# sch_buttons.net
KiCad netlist of a schematic drawn in EasyEDA
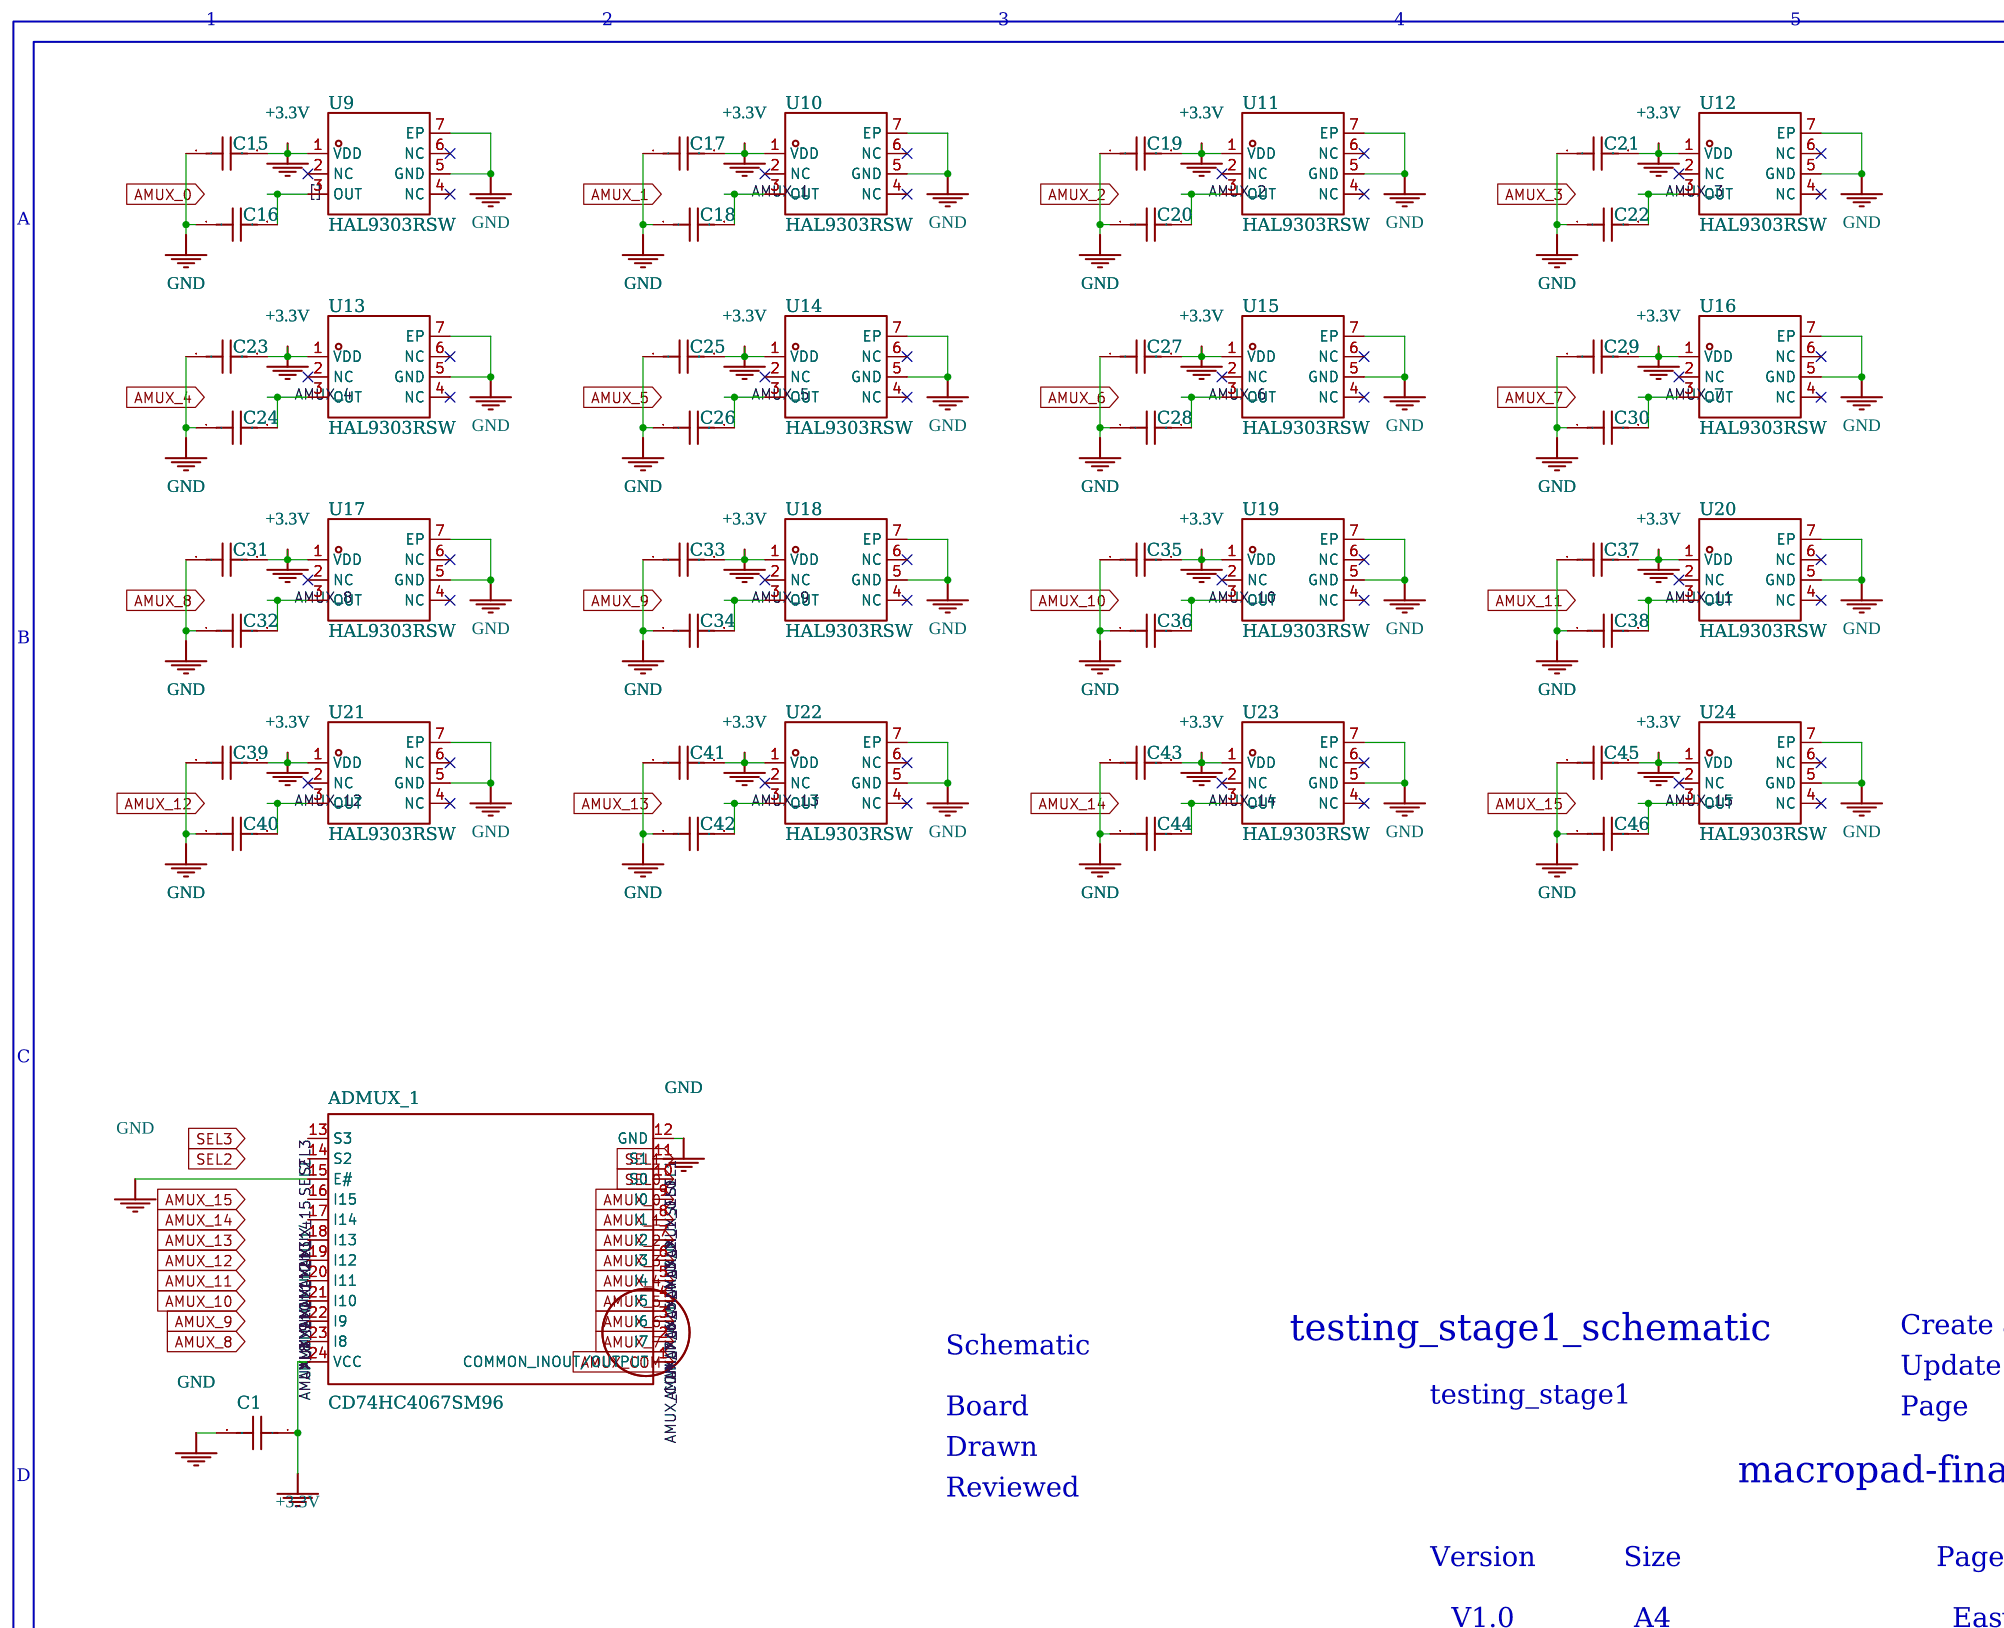
[diagram p0: schematic sheet]

(export (version "E")
  (design (tool "Eeschema 10.0.6"))
  (components
    (comp (ref "ADMUX_1")
      (value "CD74HC4067SM96")
      (fields (field (name "Manufacturer") "TI(德州仪器)"))
      (libsource (lib "") (part "Unknown_255_-240"))
    )
    (comp (ref "C1")
      (value "100nF")
      (fields
        (field (name "Manufacturer Part") "TCC0201X7R104K160ZT")
        (field (name "Manufacturer") "CCTC(三环)")
      )
      (libsource (lib "") (part "Unknown_140_-150"))
    )
    (comp (ref "C15")
      (value "100nF")
      (fields
        (field (name "Manufacturer Part") "TCC0201X7R104K160ZT")
        (field (name "Manufacturer") "CCTC(三环)")
      )
      (libsource (lib "") (part "Unknown_125_-780"))
    )
    (comp (ref "C16")
      (value "100nF")
      (fields
        (field (name "Manufacturer Part") "TCC0201X7R104K160ZT")
        (field (name "Manufacturer") "CCTC(三环)")
      )
      (libsource (lib "") (part "Unknown_130_-745"))
    )
    (comp (ref "C17")
      (value "100nF")
      (fields
        (field (name "Manufacturer Part") "TCC0201X7R104K160ZT")
        (field (name "Manufacturer") "CCTC(三环)")
      )
      (libsource (lib "") (part "Unknown_350_-780"))
    )
    (comp (ref "C18")
      (value "100nF")
      (fields
        (field (name "Manufacturer Part") "TCC0201X7R104K160ZT")
        (field (name "Manufacturer") "CCTC(三环)")
      )
      (libsource (lib "") (part "Unknown_355_-745"))
    )
    (comp (ref "C19")
      (value "100nF")
      (fields
        (field (name "Manufacturer Part") "TCC0201X7R104K160ZT")
        (field (name "Manufacturer") "CCTC(三环)")
      )
      (libsource (lib "") (part "Unknown_575_-780"))
    )
    (comp (ref "C20")
      (value "100nF")
      (fields
        (field (name "Manufacturer Part") "TCC0201X7R104K160ZT")
        (field (name "Manufacturer") "CCTC(三环)")
      )
      (libsource (lib "") (part "Unknown_580_-745"))
    )
    (comp (ref "C21")
      (value "100nF")
      (fields
        (field (name "Manufacturer Part") "TCC0201X7R104K160ZT")
        (field (name "Manufacturer") "CCTC(三环)")
      )
      (libsource (lib "") (part "Unknown_800_-780"))
    )
    (comp (ref "C22")
      (value "100nF")
      (fields
        (field (name "Manufacturer Part") "TCC0201X7R104K160ZT")
        (field (name "Manufacturer") "CCTC(三环)")
      )
      (libsource (lib "") (part "Unknown_805_-745"))
    )
    (comp (ref "C23")
      (value "100nF")
      (fields
        (field (name "Manufacturer Part") "TCC0201X7R104K160ZT")
        (field (name "Manufacturer") "CCTC(三环)")
      )
      (libsource (lib "") (part "Unknown_125_-680"))
    )
    (comp (ref "C24")
      (value "100nF")
      (fields
        (field (name "Manufacturer Part") "TCC0201X7R104K160ZT")
        (field (name "Manufacturer") "CCTC(三环)")
      )
      (libsource (lib "") (part "Unknown_130_-645"))
    )
    (comp (ref "C25")
      (value "100nF")
      (fields
        (field (name "Manufacturer Part") "TCC0201X7R104K160ZT")
        (field (name "Manufacturer") "CCTC(三环)")
      )
      (libsource (lib "") (part "Unknown_350_-680"))
    )
    (comp (ref "C26")
      (value "100nF")
      (fields
        (field (name "Manufacturer Part") "TCC0201X7R104K160ZT")
        (field (name "Manufacturer") "CCTC(三环)")
      )
      (libsource (lib "") (part "Unknown_355_-645"))
    )
    (comp (ref "C27")
      (value "100nF")
      (fields
        (field (name "Manufacturer Part") "TCC0201X7R104K160ZT")
        (field (name "Manufacturer") "CCTC(三环)")
      )
      (libsource (lib "") (part "Unknown_575_-680"))
    )
    (comp (ref "C28")
      (value "100nF")
      (fields
        (field (name "Manufacturer Part") "TCC0201X7R104K160ZT")
        (field (name "Manufacturer") "CCTC(三环)")
      )
      (libsource (lib "") (part "Unknown_580_-645"))
    )
    (comp (ref "C29")
      (value "100nF")
      (fields
        (field (name "Manufacturer Part") "TCC0201X7R104K160ZT")
        (field (name "Manufacturer") "CCTC(三环)")
      )
      (libsource (lib "") (part "Unknown_800_-680"))
    )
    (comp (ref "C30")
      (value "100nF")
      (fields
        (field (name "Manufacturer Part") "TCC0201X7R104K160ZT")
        (field (name "Manufacturer") "CCTC(三环)")
      )
      (libsource (lib "") (part "Unknown_805_-645"))
    )
    (comp (ref "C31")
      (value "100nF")
      (fields
        (field (name "Manufacturer Part") "TCC0201X7R104K160ZT")
        (field (name "Manufacturer") "CCTC(三环)")
      )
      (libsource (lib "") (part "Unknown_125_-580"))
    )
    (comp (ref "C32")
      (value "100nF")
      (fields
        (field (name "Manufacturer Part") "TCC0201X7R104K160ZT")
        (field (name "Manufacturer") "CCTC(三环)")
      )
      (libsource (lib "") (part "Unknown_130_-545"))
    )
    (comp (ref "C33")
      (value "100nF")
      (fields
        (field (name "Manufacturer Part") "TCC0201X7R104K160ZT")
        (field (name "Manufacturer") "CCTC(三环)")
      )
      (libsource (lib "") (part "Unknown_350_-580"))
    )
    (comp (ref "C34")
      (value "100nF")
      (fields
        (field (name "Manufacturer Part") "TCC0201X7R104K160ZT")
        (field (name "Manufacturer") "CCTC(三环)")
      )
      (libsource (lib "") (part "Unknown_355_-545"))
    )
    (comp (ref "C35")
      (value "100nF")
      (fields
        (field (name "Manufacturer Part") "TCC0201X7R104K160ZT")
        (field (name "Manufacturer") "CCTC(三环)")
      )
      (libsource (lib "") (part "Unknown_575_-580"))
    )
    (comp (ref "C36")
      (value "100nF")
      (fields
        (field (name "Manufacturer Part") "TCC0201X7R104K160ZT")
        (field (name "Manufacturer") "CCTC(三环)")
      )
      (libsource (lib "") (part "Unknown_580_-545"))
    )
    (comp (ref "C37")
      (value "100nF")
      (fields
        (field (name "Manufacturer Part") "TCC0201X7R104K160ZT")
        (field (name "Manufacturer") "CCTC(三环)")
      )
      (libsource (lib "") (part "Unknown_800_-580"))
    )
    (comp (ref "C38")
      (value "100nF")
      (fields
        (field (name "Manufacturer Part") "TCC0201X7R104K160ZT")
        (field (name "Manufacturer") "CCTC(三环)")
      )
      (libsource (lib "") (part "Unknown_805_-545"))
    )
    (comp (ref "C39")
      (value "100nF")
      (fields
        (field (name "Manufacturer Part") "TCC0201X7R104K160ZT")
        (field (name "Manufacturer") "CCTC(三环)")
      )
      (libsource (lib "") (part "Unknown_125_-480"))
    )
    (comp (ref "C40")
      (value "100nF")
      (fields
        (field (name "Manufacturer Part") "TCC0201X7R104K160ZT")
        (field (name "Manufacturer") "CCTC(三环)")
      )
      (libsource (lib "") (part "Unknown_130_-445"))
    )
    (comp (ref "C41")
      (value "100nF")
      (fields
        (field (name "Manufacturer Part") "TCC0201X7R104K160ZT")
        (field (name "Manufacturer") "CCTC(三环)")
      )
      (libsource (lib "") (part "Unknown_350_-480"))
    )
    (comp (ref "C42")
      (value "100nF")
      (fields
        (field (name "Manufacturer Part") "TCC0201X7R104K160ZT")
        (field (name "Manufacturer") "CCTC(三环)")
      )
      (libsource (lib "") (part "Unknown_355_-445"))
    )
    (comp (ref "C43")
      (value "100nF")
      (fields
        (field (name "Manufacturer Part") "TCC0201X7R104K160ZT")
        (field (name "Manufacturer") "CCTC(三环)")
      )
      (libsource (lib "") (part "Unknown_575_-480"))
    )
    (comp (ref "C44")
      (value "100nF")
      (fields
        (field (name "Manufacturer Part") "TCC0201X7R104K160ZT")
        (field (name "Manufacturer") "CCTC(三环)")
      )
      (libsource (lib "") (part "Unknown_580_-445"))
    )
    (comp (ref "C45")
      (value "100nF")
      (fields
        (field (name "Manufacturer Part") "TCC0201X7R104K160ZT")
        (field (name "Manufacturer") "CCTC(三环)")
      )
      (libsource (lib "") (part "Unknown_800_-480"))
    )
    (comp (ref "C46")
      (value "100nF")
      (fields
        (field (name "Manufacturer Part") "TCC0201X7R104K160ZT")
        (field (name "Manufacturer") "CCTC(三环)")
      )
      (libsource (lib "") (part "Unknown_805_-445"))
    )
    (comp (ref "U9")
      (value "HAL9303RSW")
      (fields (field (name "Manufacturer") "Hallwee(霍尔微电子)"))
      (libsource (lib "") (part "Unknown_200_-775"))
    )
    (comp (ref "U10")
      (value "HAL9303RSW")
      (fields (field (name "Manufacturer") "Hallwee(霍尔微电子)"))
      (libsource (lib "") (part "Unknown_425_-775"))
    )
    (comp (ref "U11")
      (value "HAL9303RSW")
      (fields (field (name "Manufacturer") "Hallwee(霍尔微电子)"))
      (libsource (lib "") (part "Unknown_650_-775"))
    )
    (comp (ref "U12")
      (value "HAL9303RSW")
      (fields (field (name "Manufacturer") "Hallwee(霍尔微电子)"))
      (libsource (lib "") (part "Unknown_875_-775"))
    )
    (comp (ref "U13")
      (value "HAL9303RSW")
      (fields (field (name "Manufacturer") "Hallwee(霍尔微电子)"))
      (libsource (lib "") (part "Unknown_200_-675"))
    )
    (comp (ref "U14")
      (value "HAL9303RSW")
      (fields (field (name "Manufacturer") "Hallwee(霍尔微电子)"))
      (libsource (lib "") (part "Unknown_425_-675"))
    )
    (comp (ref "U15")
      (value "HAL9303RSW")
      (fields (field (name "Manufacturer") "Hallwee(霍尔微电子)"))
      (libsource (lib "") (part "Unknown_650_-675"))
    )
    (comp (ref "U16")
      (value "HAL9303RSW")
      (fields (field (name "Manufacturer") "Hallwee(霍尔微电子)"))
      (libsource (lib "") (part "Unknown_875_-675"))
    )
    (comp (ref "U17")
      (value "HAL9303RSW")
      (fields (field (name "Manufacturer") "Hallwee(霍尔微电子)"))
      (libsource (lib "") (part "Unknown_200_-575"))
    )
    (comp (ref "U18")
      (value "HAL9303RSW")
      (fields (field (name "Manufacturer") "Hallwee(霍尔微电子)"))
      (libsource (lib "") (part "Unknown_425_-575"))
    )
    (comp (ref "U19")
      (value "HAL9303RSW")
      (fields (field (name "Manufacturer") "Hallwee(霍尔微电子)"))
      (libsource (lib "") (part "Unknown_650_-575"))
    )
    (comp (ref "U20")
      (value "HAL9303RSW")
      (fields (field (name "Manufacturer") "Hallwee(霍尔微电子)"))
      (libsource (lib "") (part "Unknown_875_-575"))
    )
    (comp (ref "U21")
      (value "HAL9303RSW")
      (fields (field (name "Manufacturer") "Hallwee(霍尔微电子)"))
      (libsource (lib "") (part "Unknown_200_-475"))
    )
    (comp (ref "U22")
      (value "HAL9303RSW")
      (fields (field (name "Manufacturer") "Hallwee(霍尔微电子)"))
      (libsource (lib "") (part "Unknown_425_-475"))
    )
    (comp (ref "U23")
      (value "HAL9303RSW")
      (fields (field (name "Manufacturer") "Hallwee(霍尔微电子)"))
      (libsource (lib "") (part "Unknown_650_-475"))
    )
    (comp (ref "U24")
      (value "HAL9303RSW")
      (fields (field (name "Manufacturer") "Hallwee(霍尔微电子)"))
      (libsource (lib "") (part "Unknown_875_-475"))
    )
  )
  (nets
    (net (code "1") (name "+3.3V") (class "Default")
      (node (ref "ADMUX_1") (pin "24") (pinfunction "VCC_24") (pintype "unspecified"))
      (node (ref "C1") (pin "1") (pinfunction "1_1") (pintype "unspecified"))
      (node (ref "C15") (pin "2") (pinfunction "2_2") (pintype "unspecified"))
      (node (ref "C17") (pin "2") (pinfunction "2_2") (pintype "unspecified"))
      (node (ref "C19") (pin "2") (pinfunction "2_2") (pintype "unspecified"))
      (node (ref "C21") (pin "2") (pinfunction "2_2") (pintype "unspecified"))
      (node (ref "C23") (pin "2") (pinfunction "2_2") (pintype "unspecified"))
      (node (ref "C25") (pin "2") (pinfunction "2_2") (pintype "unspecified"))
      (node (ref "C27") (pin "2") (pinfunction "2_2") (pintype "unspecified"))
      (node (ref "C29") (pin "2") (pinfunction "2_2") (pintype "unspecified"))
      (node (ref "C31") (pin "2") (pinfunction "2_2") (pintype "unspecified"))
      (node (ref "C33") (pin "2") (pinfunction "2_2") (pintype "unspecified"))
      (node (ref "C35") (pin "2") (pinfunction "2_2") (pintype "unspecified"))
      (node (ref "C37") (pin "2") (pinfunction "2_2") (pintype "unspecified"))
      (node (ref "C39") (pin "2") (pinfunction "2_2") (pintype "unspecified"))
      (node (ref "C41") (pin "2") (pinfunction "2_2") (pintype "unspecified"))
      (node (ref "C43") (pin "2") (pinfunction "2_2") (pintype "unspecified"))
      (node (ref "C45") (pin "2") (pinfunction "2_2") (pintype "unspecified"))
      (node (ref "U10") (pin "1") (pinfunction "VDD_1") (pintype "unspecified"))
      (node (ref "U11") (pin "1") (pinfunction "VDD_1") (pintype "unspecified"))
      (node (ref "U12") (pin "1") (pinfunction "VDD_1") (pintype "unspecified"))
      (node (ref "U13") (pin "1") (pinfunction "VDD_1") (pintype "unspecified"))
      (node (ref "U14") (pin "1") (pinfunction "VDD_1") (pintype "unspecified"))
      (node (ref "U15") (pin "1") (pinfunction "VDD_1") (pintype "unspecified"))
      (node (ref "U16") (pin "1") (pinfunction "VDD_1") (pintype "unspecified"))
      (node (ref "U17") (pin "1") (pinfunction "VDD_1") (pintype "unspecified"))
      (node (ref "U18") (pin "1") (pinfunction "VDD_1") (pintype "unspecified"))
      (node (ref "U19") (pin "1") (pinfunction "VDD_1") (pintype "unspecified"))
      (node (ref "U20") (pin "1") (pinfunction "VDD_1") (pintype "unspecified"))
      (node (ref "U21") (pin "1") (pinfunction "VDD_1") (pintype "unspecified"))
      (node (ref "U22") (pin "1") (pinfunction "VDD_1") (pintype "unspecified"))
      (node (ref "U23") (pin "1") (pinfunction "VDD_1") (pintype "unspecified"))
      (node (ref "U24") (pin "1") (pinfunction "VDD_1") (pintype "unspecified"))
      (node (ref "U9") (pin "1") (pinfunction "VDD_1") (pintype "unspecified"))
    )
    (net (code "2") (name "/[]") (class "Default")
      (node (ref "C16") (pin "2") (pinfunction "2_2") (pintype "unspecified"))
      (node (ref "U9") (pin "3") (pinfunction "OUT_3") (pintype "unspecified"))
    )
    (net (code "3") (name "AMUX_0") (class "Default")
      (node (ref "ADMUX_1") (pin "9") (pinfunction "I0_9") (pintype "unspecified"))
    )
    (net (code "4") (name "AMUX_1") (class "Default")
      (node (ref "ADMUX_1") (pin "8") (pinfunction "I1_8") (pintype "unspecified"))
      (node (ref "C18") (pin "2") (pinfunction "2_2") (pintype "unspecified"))
      (node (ref "U10") (pin "3") (pinfunction "OUT_3") (pintype "unspecified"))
    )
    (net (code "5") (name "AMUX_2") (class "Default")
      (node (ref "ADMUX_1") (pin "7") (pinfunction "I2_7") (pintype "unspecified"))
      (node (ref "C20") (pin "2") (pinfunction "2_2") (pintype "unspecified"))
      (node (ref "U11") (pin "3") (pinfunction "OUT_3") (pintype "unspecified"))
    )
    (net (code "6") (name "AMUX_3") (class "Default")
      (node (ref "ADMUX_1") (pin "6") (pinfunction "I3_6") (pintype "unspecified"))
      (node (ref "C22") (pin "2") (pinfunction "2_2") (pintype "unspecified"))
      (node (ref "U12") (pin "3") (pinfunction "OUT_3") (pintype "unspecified"))
    )
    (net (code "7") (name "AMUX_4") (class "Default")
      (node (ref "ADMUX_1") (pin "5") (pinfunction "I4_5") (pintype "unspecified"))
      (node (ref "C24") (pin "2") (pinfunction "2_2") (pintype "unspecified"))
      (node (ref "U13") (pin "3") (pinfunction "OUT_3") (pintype "unspecified"))
    )
    (net (code "8") (name "AMUX_5") (class "Default")
      (node (ref "ADMUX_1") (pin "4") (pinfunction "I5_4") (pintype "unspecified"))
      (node (ref "C26") (pin "2") (pinfunction "2_2") (pintype "unspecified"))
      (node (ref "U14") (pin "3") (pinfunction "OUT_3") (pintype "unspecified"))
    )
    (net (code "9") (name "AMUX_6") (class "Default")
      (node (ref "ADMUX_1") (pin "3") (pinfunction "I6_3") (pintype "unspecified"))
      (node (ref "C28") (pin "2") (pinfunction "2_2") (pintype "unspecified"))
      (node (ref "U15") (pin "3") (pinfunction "OUT_3") (pintype "unspecified"))
    )
    (net (code "10") (name "AMUX_7") (class "Default")
      (node (ref "ADMUX_1") (pin "2") (pinfunction "I7_2") (pintype "unspecified"))
      (node (ref "C30") (pin "2") (pinfunction "2_2") (pintype "unspecified"))
      (node (ref "U16") (pin "3") (pinfunction "OUT_3") (pintype "unspecified"))
    )
    (net (code "11") (name "AMUX_8") (class "Default")
      (node (ref "ADMUX_1") (pin "23") (pinfunction "I8_23") (pintype "unspecified"))
      (node (ref "C32") (pin "2") (pinfunction "2_2") (pintype "unspecified"))
      (node (ref "U17") (pin "3") (pinfunction "OUT_3") (pintype "unspecified"))
    )
    (net (code "12") (name "AMUX_9") (class "Default")
      (node (ref "ADMUX_1") (pin "22") (pinfunction "I9_22") (pintype "unspecified"))
      (node (ref "C34") (pin "2") (pinfunction "2_2") (pintype "unspecified"))
      (node (ref "U18") (pin "3") (pinfunction "OUT_3") (pintype "unspecified"))
    )
    (net (code "13") (name "AMUX_10") (class "Default")
      (node (ref "ADMUX_1") (pin "21") (pinfunction "I10_21") (pintype "unspecified"))
      (node (ref "C36") (pin "2") (pinfunction "2_2") (pintype "unspecified"))
      (node (ref "U19") (pin "3") (pinfunction "OUT_3") (pintype "unspecified"))
    )
    (net (code "14") (name "AMUX_11") (class "Default")
      (node (ref "ADMUX_1") (pin "20") (pinfunction "I11_20") (pintype "unspecified"))
      (node (ref "C38") (pin "2") (pinfunction "2_2") (pintype "unspecified"))
      (node (ref "U20") (pin "3") (pinfunction "OUT_3") (pintype "unspecified"))
    )
    (net (code "15") (name "AMUX_12") (class "Default")
      (node (ref "ADMUX_1") (pin "19") (pinfunction "I12_19") (pintype "unspecified"))
      (node (ref "C40") (pin "2") (pinfunction "2_2") (pintype "unspecified"))
      (node (ref "U21") (pin "3") (pinfunction "OUT_3") (pintype "unspecified"))
    )
    (net (code "16") (name "AMUX_13") (class "Default")
      (node (ref "ADMUX_1") (pin "18") (pinfunction "I13_18") (pintype "unspecified"))
      (node (ref "C42") (pin "2") (pinfunction "2_2") (pintype "unspecified"))
      (node (ref "U22") (pin "3") (pinfunction "OUT_3") (pintype "unspecified"))
    )
    (net (code "17") (name "AMUX_14") (class "Default")
      (node (ref "ADMUX_1") (pin "17") (pinfunction "I14_17") (pintype "unspecified"))
      (node (ref "C44") (pin "2") (pinfunction "2_2") (pintype "unspecified"))
      (node (ref "U23") (pin "3") (pinfunction "OUT_3") (pintype "unspecified"))
    )
    (net (code "18") (name "AMUX_15") (class "Default")
      (node (ref "ADMUX_1") (pin "16") (pinfunction "I15_16") (pintype "unspecified"))
      (node (ref "C46") (pin "2") (pinfunction "2_2") (pintype "unspecified"))
      (node (ref "U24") (pin "3") (pinfunction "OUT_3") (pintype "unspecified"))
    )
    (net (code "19") (name "AMUX_COM") (class "Default")
      (node (ref "ADMUX_1") (pin "1") (pinfunction "COMMON_INOUT/OUTPUT_1") (pintype "unspecified"))
    )
    (net (code "20") (name "GND") (class "Default")
      (node (ref "ADMUX_1") (pin "12") (pinfunction "GND_12") (pintype "unspecified"))
      (node (ref "ADMUX_1") (pin "15") (pinfunction "E#_15") (pintype "unspecified"))
      (node (ref "C1") (pin "2") (pinfunction "2_2") (pintype "unspecified"))
      (node (ref "C15") (pin "1") (pinfunction "1_1") (pintype "unspecified"))
      (node (ref "C16") (pin "1") (pinfunction "1_1") (pintype "unspecified"))
      (node (ref "C17") (pin "1") (pinfunction "1_1") (pintype "unspecified"))
      (node (ref "C18") (pin "1") (pinfunction "1_1") (pintype "unspecified"))
      (node (ref "C19") (pin "1") (pinfunction "1_1") (pintype "unspecified"))
      (node (ref "C20") (pin "1") (pinfunction "1_1") (pintype "unspecified"))
      (node (ref "C21") (pin "1") (pinfunction "1_1") (pintype "unspecified"))
      (node (ref "C22") (pin "1") (pinfunction "1_1") (pintype "unspecified"))
      (node (ref "C23") (pin "1") (pinfunction "1_1") (pintype "unspecified"))
      (node (ref "C24") (pin "1") (pinfunction "1_1") (pintype "unspecified"))
      (node (ref "C25") (pin "1") (pinfunction "1_1") (pintype "unspecified"))
      (node (ref "C26") (pin "1") (pinfunction "1_1") (pintype "unspecified"))
      (node (ref "C27") (pin "1") (pinfunction "1_1") (pintype "unspecified"))
      (node (ref "C28") (pin "1") (pinfunction "1_1") (pintype "unspecified"))
      (node (ref "C29") (pin "1") (pinfunction "1_1") (pintype "unspecified"))
      (node (ref "C30") (pin "1") (pinfunction "1_1") (pintype "unspecified"))
      (node (ref "C31") (pin "1") (pinfunction "1_1") (pintype "unspecified"))
      (node (ref "C32") (pin "1") (pinfunction "1_1") (pintype "unspecified"))
      (node (ref "C33") (pin "1") (pinfunction "1_1") (pintype "unspecified"))
      (node (ref "C34") (pin "1") (pinfunction "1_1") (pintype "unspecified"))
      (node (ref "C35") (pin "1") (pinfunction "1_1") (pintype "unspecified"))
      (node (ref "C36") (pin "1") (pinfunction "1_1") (pintype "unspecified"))
      (node (ref "C37") (pin "1") (pinfunction "1_1") (pintype "unspecified"))
      (node (ref "C38") (pin "1") (pinfunction "1_1") (pintype "unspecified"))
      (node (ref "C39") (pin "1") (pinfunction "1_1") (pintype "unspecified"))
      (node (ref "C40") (pin "1") (pinfunction "1_1") (pintype "unspecified"))
      (node (ref "C41") (pin "1") (pinfunction "1_1") (pintype "unspecified"))
      (node (ref "C42") (pin "1") (pinfunction "1_1") (pintype "unspecified"))
      (node (ref "C43") (pin "1") (pinfunction "1_1") (pintype "unspecified"))
      (node (ref "C44") (pin "1") (pinfunction "1_1") (pintype "unspecified"))
      (node (ref "C45") (pin "1") (pinfunction "1_1") (pintype "unspecified"))
      (node (ref "C46") (pin "1") (pinfunction "1_1") (pintype "unspecified"))
      (node (ref "U10") (pin "5") (pinfunction "GND_5") (pintype "unspecified"))
      (node (ref "U10") (pin "7") (pinfunction "EP_7") (pintype "unspecified"))
      (node (ref "U11") (pin "5") (pinfunction "GND_5") (pintype "unspecified"))
      (node (ref "U11") (pin "7") (pinfunction "EP_7") (pintype "unspecified"))
      (node (ref "U12") (pin "5") (pinfunction "GND_5") (pintype "unspecified"))
      (node (ref "U12") (pin "7") (pinfunction "EP_7") (pintype "unspecified"))
      (node (ref "U13") (pin "5") (pinfunction "GND_5") (pintype "unspecified"))
      (node (ref "U13") (pin "7") (pinfunction "EP_7") (pintype "unspecified"))
      (node (ref "U14") (pin "5") (pinfunction "GND_5") (pintype "unspecified"))
      (node (ref "U14") (pin "7") (pinfunction "EP_7") (pintype "unspecified"))
      (node (ref "U15") (pin "5") (pinfunction "GND_5") (pintype "unspecified"))
      (node (ref "U15") (pin "7") (pinfunction "EP_7") (pintype "unspecified"))
      (node (ref "U16") (pin "5") (pinfunction "GND_5") (pintype "unspecified"))
      (node (ref "U16") (pin "7") (pinfunction "EP_7") (pintype "unspecified"))
      (node (ref "U17") (pin "5") (pinfunction "GND_5") (pintype "unspecified"))
      (node (ref "U17") (pin "7") (pinfunction "EP_7") (pintype "unspecified"))
      (node (ref "U18") (pin "5") (pinfunction "GND_5") (pintype "unspecified"))
      (node (ref "U18") (pin "7") (pinfunction "EP_7") (pintype "unspecified"))
      (node (ref "U19") (pin "5") (pinfunction "GND_5") (pintype "unspecified"))
      (node (ref "U19") (pin "7") (pinfunction "EP_7") (pintype "unspecified"))
      (node (ref "U20") (pin "5") (pinfunction "GND_5") (pintype "unspecified"))
      (node (ref "U20") (pin "7") (pinfunction "EP_7") (pintype "unspecified"))
      (node (ref "U21") (pin "5") (pinfunction "GND_5") (pintype "unspecified"))
      (node (ref "U21") (pin "7") (pinfunction "EP_7") (pintype "unspecified"))
      (node (ref "U22") (pin "5") (pinfunction "GND_5") (pintype "unspecified"))
      (node (ref "U22") (pin "7") (pinfunction "EP_7") (pintype "unspecified"))
      (node (ref "U23") (pin "5") (pinfunction "GND_5") (pintype "unspecified"))
      (node (ref "U23") (pin "7") (pinfunction "EP_7") (pintype "unspecified"))
      (node (ref "U24") (pin "5") (pinfunction "GND_5") (pintype "unspecified"))
      (node (ref "U24") (pin "7") (pinfunction "EP_7") (pintype "unspecified"))
      (node (ref "U9") (pin "5") (pinfunction "GND_5") (pintype "unspecified"))
      (node (ref "U9") (pin "7") (pinfunction "EP_7") (pintype "unspecified"))
    )
    (net (code "21") (name "SEL0") (class "Default")
      (node (ref "ADMUX_1") (pin "10") (pinfunction "S0_10") (pintype "unspecified"))
    )
    (net (code "22") (name "SEL1") (class "Default")
      (node (ref "ADMUX_1") (pin "11") (pinfunction "S1_11") (pintype "unspecified"))
    )
    (net (code "23") (name "SEL2") (class "Default")
      (node (ref "ADMUX_1") (pin "14") (pinfunction "S2_14") (pintype "unspecified"))
    )
    (net (code "24") (name "SEL3") (class "Default")
      (node (ref "ADMUX_1") (pin "13") (pinfunction "S3_13") (pintype "unspecified"))
    )
    (net (code "25") (name "unconnected-(U9-NC-Pad2)") (class "Default")
      (node (ref "U9") (pin "2") (pinfunction "NC_2") (pintype "unspecified+no_connect"))
    )
    (net (code "26") (name "unconnected-(U9-NC-Pad4)") (class "Default")
      (node (ref "U9") (pin "4") (pinfunction "NC_4") (pintype "unspecified+no_connect"))
    )
    (net (code "27") (name "unconnected-(U9-NC-Pad6)") (class "Default")
      (node (ref "U9") (pin "6") (pinfunction "NC_6") (pintype "unspecified+no_connect"))
    )
    (net (code "28") (name "unconnected-(U10-NC-Pad2)") (class "Default")
      (node (ref "U10") (pin "2") (pinfunction "NC_2") (pintype "unspecified+no_connect"))
    )
    (net (code "29") (name "unconnected-(U10-NC-Pad4)") (class "Default")
      (node (ref "U10") (pin "4") (pinfunction "NC_4") (pintype "unspecified+no_connect"))
    )
    (net (code "30") (name "unconnected-(U10-NC-Pad6)") (class "Default")
      (node (ref "U10") (pin "6") (pinfunction "NC_6") (pintype "unspecified+no_connect"))
    )
    (net (code "31") (name "unconnected-(U11-NC-Pad2)") (class "Default")
      (node (ref "U11") (pin "2") (pinfunction "NC_2") (pintype "unspecified+no_connect"))
    )
    (net (code "32") (name "unconnected-(U11-NC-Pad4)") (class "Default")
      (node (ref "U11") (pin "4") (pinfunction "NC_4") (pintype "unspecified+no_connect"))
    )
    (net (code "33") (name "unconnected-(U11-NC-Pad6)") (class "Default")
      (node (ref "U11") (pin "6") (pinfunction "NC_6") (pintype "unspecified+no_connect"))
    )
    (net (code "34") (name "unconnected-(U12-NC-Pad2)") (class "Default")
      (node (ref "U12") (pin "2") (pinfunction "NC_2") (pintype "unspecified+no_connect"))
    )
    (net (code "35") (name "unconnected-(U12-NC-Pad4)") (class "Default")
      (node (ref "U12") (pin "4") (pinfunction "NC_4") (pintype "unspecified+no_connect"))
    )
    (net (code "36") (name "unconnected-(U12-NC-Pad6)") (class "Default")
      (node (ref "U12") (pin "6") (pinfunction "NC_6") (pintype "unspecified+no_connect"))
    )
    (net (code "37") (name "unconnected-(U13-NC-Pad2)") (class "Default")
      (node (ref "U13") (pin "2") (pinfunction "NC_2") (pintype "unspecified+no_connect"))
    )
    (net (code "38") (name "unconnected-(U13-NC-Pad4)") (class "Default")
      (node (ref "U13") (pin "4") (pinfunction "NC_4") (pintype "unspecified+no_connect"))
    )
    (net (code "39") (name "unconnected-(U13-NC-Pad6)") (class "Default")
      (node (ref "U13") (pin "6") (pinfunction "NC_6") (pintype "unspecified+no_connect"))
    )
    (net (code "40") (name "unconnected-(U14-NC-Pad2)") (class "Default")
      (node (ref "U14") (pin "2") (pinfunction "NC_2") (pintype "unspecified+no_connect"))
    )
    (net (code "41") (name "unconnected-(U14-NC-Pad4)") (class "Default")
      (node (ref "U14") (pin "4") (pinfunction "NC_4") (pintype "unspecified+no_connect"))
    )
    (net (code "42") (name "unconnected-(U14-NC-Pad6)") (class "Default")
      (node (ref "U14") (pin "6") (pinfunction "NC_6") (pintype "unspecified+no_connect"))
    )
    (net (code "43") (name "unconnected-(U15-NC-Pad2)") (class "Default")
      (node (ref "U15") (pin "2") (pinfunction "NC_2") (pintype "unspecified+no_connect"))
    )
    (net (code "44") (name "unconnected-(U15-NC-Pad4)") (class "Default")
      (node (ref "U15") (pin "4") (pinfunction "NC_4") (pintype "unspecified+no_connect"))
    )
    (net (code "45") (name "unconnected-(U15-NC-Pad6)") (class "Default")
      (node (ref "U15") (pin "6") (pinfunction "NC_6") (pintype "unspecified+no_connect"))
    )
    (net (code "46") (name "unconnected-(U16-NC-Pad2)") (class "Default")
      (node (ref "U16") (pin "2") (pinfunction "NC_2") (pintype "unspecified+no_connect"))
    )
    (net (code "47") (name "unconnected-(U16-NC-Pad4)") (class "Default")
      (node (ref "U16") (pin "4") (pinfunction "NC_4") (pintype "unspecified+no_connect"))
    )
    (net (code "48") (name "unconnected-(U16-NC-Pad6)") (class "Default")
      (node (ref "U16") (pin "6") (pinfunction "NC_6") (pintype "unspecified+no_connect"))
    )
    (net (code "49") (name "unconnected-(U17-NC-Pad2)") (class "Default")
      (node (ref "U17") (pin "2") (pinfunction "NC_2") (pintype "unspecified+no_connect"))
    )
    (net (code "50") (name "unconnected-(U17-NC-Pad4)") (class "Default")
      (node (ref "U17") (pin "4") (pinfunction "NC_4") (pintype "unspecified+no_connect"))
    )
    (net (code "51") (name "unconnected-(U17-NC-Pad6)") (class "Default")
      (node (ref "U17") (pin "6") (pinfunction "NC_6") (pintype "unspecified+no_connect"))
    )
    (net (code "52") (name "unconnected-(U18-NC-Pad2)") (class "Default")
      (node (ref "U18") (pin "2") (pinfunction "NC_2") (pintype "unspecified+no_connect"))
    )
    (net (code "53") (name "unconnected-(U18-NC-Pad4)") (class "Default")
      (node (ref "U18") (pin "4") (pinfunction "NC_4") (pintype "unspecified+no_connect"))
    )
    (net (code "54") (name "unconnected-(U18-NC-Pad6)") (class "Default")
      (node (ref "U18") (pin "6") (pinfunction "NC_6") (pintype "unspecified+no_connect"))
    )
    (net (code "55") (name "unconnected-(U19-NC-Pad2)") (class "Default")
      (node (ref "U19") (pin "2") (pinfunction "NC_2") (pintype "unspecified+no_connect"))
    )
    (net (code "56") (name "unconnected-(U19-NC-Pad4)") (class "Default")
      (node (ref "U19") (pin "4") (pinfunction "NC_4") (pintype "unspecified+no_connect"))
    )
    (net (code "57") (name "unconnected-(U19-NC-Pad6)") (class "Default")
      (node (ref "U19") (pin "6") (pinfunction "NC_6") (pintype "unspecified+no_connect"))
    )
    (net (code "58") (name "unconnected-(U20-NC-Pad2)") (class "Default")
      (node (ref "U20") (pin "2") (pinfunction "NC_2") (pintype "unspecified+no_connect"))
    )
    (net (code "59") (name "unconnected-(U20-NC-Pad4)") (class "Default")
      (node (ref "U20") (pin "4") (pinfunction "NC_4") (pintype "unspecified+no_connect"))
    )
    (net (code "60") (name "unconnected-(U20-NC-Pad6)") (class "Default")
      (node (ref "U20") (pin "6") (pinfunction "NC_6") (pintype "unspecified+no_connect"))
    )
    (net (code "61") (name "unconnected-(U21-NC-Pad2)") (class "Default")
      (node (ref "U21") (pin "2") (pinfunction "NC_2") (pintype "unspecified+no_connect"))
    )
    (net (code "62") (name "unconnected-(U21-NC-Pad4)") (class "Default")
      (node (ref "U21") (pin "4") (pinfunction "NC_4") (pintype "unspecified+no_connect"))
    )
    (net (code "63") (name "unconnected-(U21-NC-Pad6)") (class "Default")
      (node (ref "U21") (pin "6") (pinfunction "NC_6") (pintype "unspecified+no_connect"))
    )
    (net (code "64") (name "unconnected-(U22-NC-Pad2)") (class "Default")
      (node (ref "U22") (pin "2") (pinfunction "NC_2") (pintype "unspecified+no_connect"))
    )
    (net (code "65") (name "unconnected-(U22-NC-Pad4)") (class "Default")
      (node (ref "U22") (pin "4") (pinfunction "NC_4") (pintype "unspecified+no_connect"))
    )
    (net (code "66") (name "unconnected-(U22-NC-Pad6)") (class "Default")
      (node (ref "U22") (pin "6") (pinfunction "NC_6") (pintype "unspecified+no_connect"))
    )
    (net (code "67") (name "unconnected-(U23-NC-Pad2)") (class "Default")
      (node (ref "U23") (pin "2") (pinfunction "NC_2") (pintype "unspecified+no_connect"))
    )
    (net (code "68") (name "unconnected-(U23-NC-Pad4)") (class "Default")
      (node (ref "U23") (pin "4") (pinfunction "NC_4") (pintype "unspecified+no_connect"))
    )
    (net (code "69") (name "unconnected-(U23-NC-Pad6)") (class "Default")
      (node (ref "U23") (pin "6") (pinfunction "NC_6") (pintype "unspecified+no_connect"))
    )
    (net (code "70") (name "unconnected-(U24-NC-Pad2)") (class "Default")
      (node (ref "U24") (pin "2") (pinfunction "NC_2") (pintype "unspecified+no_connect"))
    )
    (net (code "71") (name "unconnected-(U24-NC-Pad4)") (class "Default")
      (node (ref "U24") (pin "4") (pinfunction "NC_4") (pintype "unspecified+no_connect"))
    )
    (net (code "72") (name "unconnected-(U24-NC-Pad6)") (class "Default")
      (node (ref "U24") (pin "6") (pinfunction "NC_6") (pintype "unspecified+no_connect"))
    )
  )
)
